# Fonte.net
KiCad netlist of a schematic drawn in Altium Designer
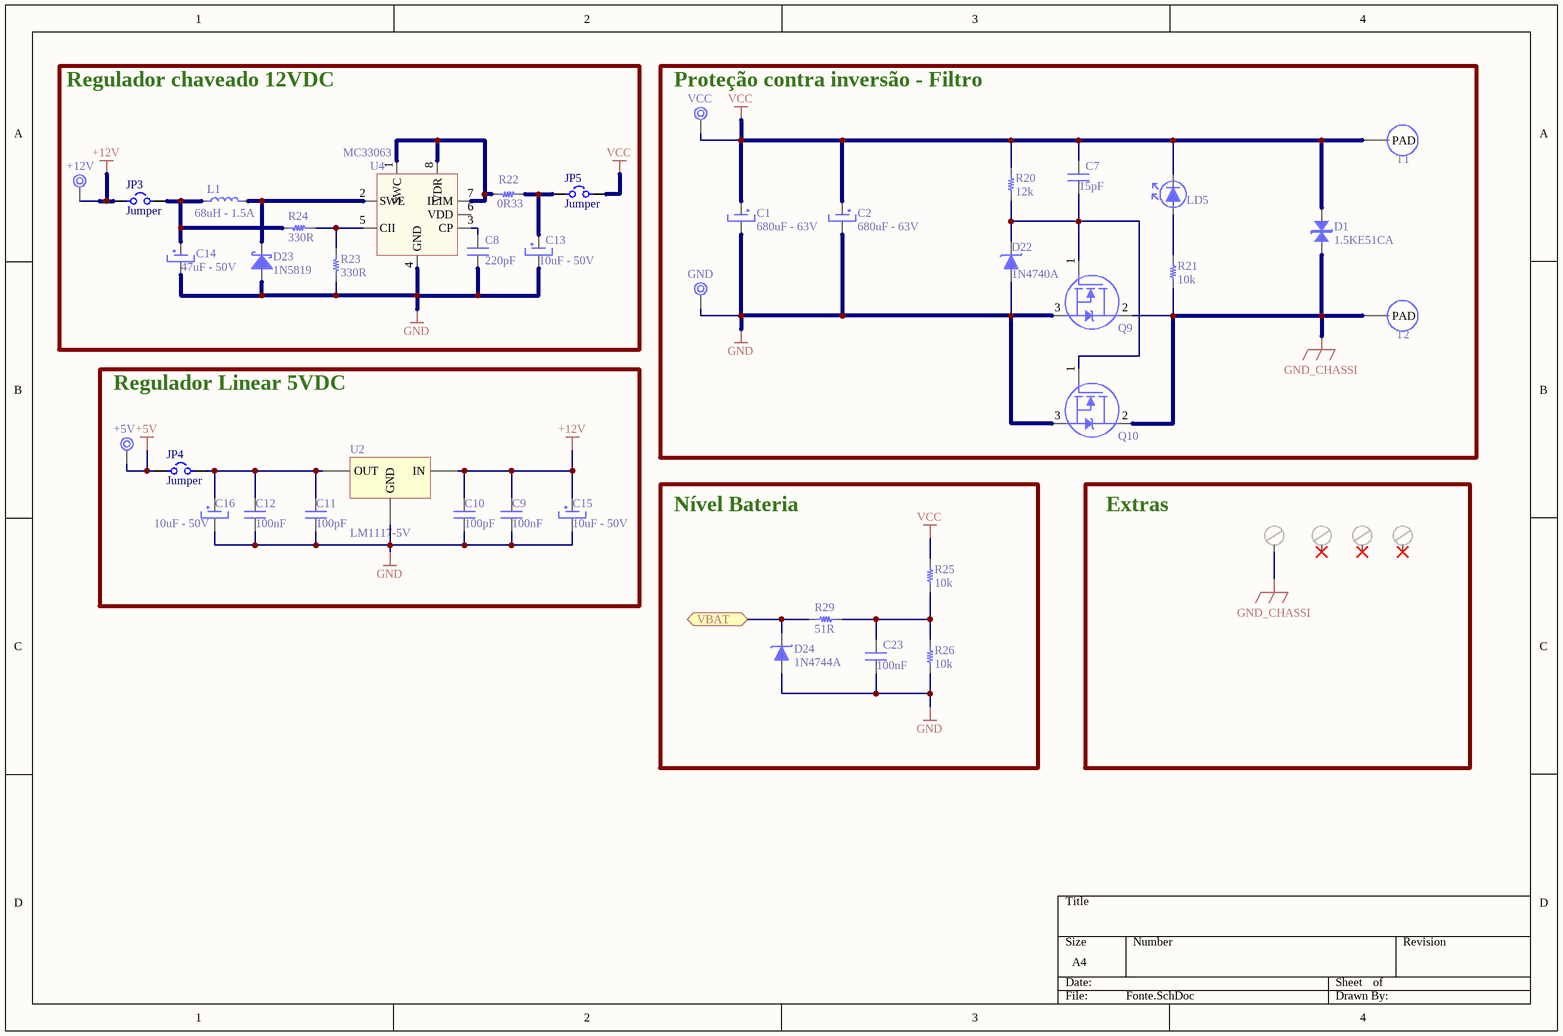
[diagram p0: Fonte.SchDoc]

(export (version "E")
  (design (tool "Eeschema 10.0.6"))
  (components
    (comp (ref "+5V") (value "+5V") (footprint "TEST_POINT") (libsource (lib "bike") (part "test_point")))
    (comp (ref "+12V") (value "+12V") (footprint "TEST_POINT") (libsource (lib "bike") (part "test_point")))
    (comp (ref "C1")
      (value "680uF - 63V")
      (footprint "Capacitor_PHT_filter")
      (description "Capacitor_680uF_63V")
      (libsource (lib "bike") (part "680uF - 63V"))
    )
    (comp (ref "C2")
      (value "680uF - 63V")
      (footprint "Capacitor_PHT_filter")
      (description "Capacitor_680uF_63V")
      (libsource (lib "bike") (part "680uF - 63V"))
    )
    (comp (ref "C7")
      (value "15pF")
      (footprint "Capacitor_0805")
      (description "Capacitor C0805 15pF")
      (libsource (lib "bike") (part "Cap0805_100nF"))
    )
    (comp (ref "C8")
      (value "220pF")
      (footprint "Capacitor_0805")
      (description "Capacitor C0805 100nF Desacoplamento")
      (libsource (lib "bike") (part "Cap0805_220pF"))
    )
    (comp (ref "C9")
      (value "100nF")
      (footprint "Capacitor_0805")
      (description "Capacitor C0805 100nF Desacoplamento")
      (libsource (lib "bike") (part "Cap0805_100nF"))
    )
    (comp (ref "C10")
      (value "100pF")
      (footprint "Capacitor_0805")
      (description "Capacitor C0805 100pF Desacoplamento")
      (libsource (lib "bike") (part "Cap0805_100nF"))
    )
    (comp (ref "C11")
      (value "100pF")
      (footprint "Capacitor_0805")
      (description "Capacitor C0805 100pF Desacoplamento")
      (libsource (lib "bike") (part "Cap0805_100nF"))
    )
    (comp (ref "C12")
      (value "100nF")
      (footprint "Capacitor_0805")
      (description "Capacitor C0805 100nF Desacoplamento")
      (libsource (lib "bike") (part "Cap0805_100nF"))
    )
    (comp (ref "C13")
      (value "10uF - 50V")
      (footprint "CAP_10x20mm")
      (description "Capacitor_10uF_50V")
      (libsource (lib "bike") (part "10uF - 50V"))
    )
    (comp (ref "C14")
      (value "47uF - 50V")
      (footprint "CAP_10x20mm")
      (description "Capacitor_47uF_50V")
      (libsource (lib "bike") (part "47uF - 50V"))
    )
    (comp (ref "C15")
      (value "10uF - 50V")
      (footprint "CAP_10x20mm")
      (description "Capacitor_10uF_50V")
      (libsource (lib "bike") (part "10uF - 50V"))
    )
    (comp (ref "C16")
      (value "10uF - 50V")
      (footprint "CAP_10x20mm")
      (description "Capacitor_10uF_50V")
      (libsource (lib "bike") (part "10uF - 50V"))
    )
    (comp (ref "C23")
      (value "100nF")
      (footprint "Capacitor_0805")
      (description "Capacitor C0805 100nF Desacoplamento")
      (libsource (lib "bike") (part "Cap0805_100nF"))
    )
    (comp (ref "D1")
      (value "1.5KE51CA")
      (footprint "DO-201")
      (description "Transzorb")
      (libsource (lib "bike") (part "1.5KE51CA"))
    )
    (comp (ref "D22")
      (value "1N4740A")
      (footprint "Diode_PHT")
      (description "Diodo Zener 10V 200mA")
      (libsource (lib "bike") (part "1N4740A"))
    )
    (comp (ref "D23")
      (value "1N5819")
      (footprint "Diode_PHT")
      (description "Diodo Schottky 40V - 1A")
      (libsource (lib "bike") (part "1N5819"))
    )
    (comp (ref "D24")
      (value "1N4744A")
      (footprint "Diode_PHT")
      (description "Diodo Zener 15V 200mA")
      (libsource (lib "bike") (part "1N4744A"))
    )
    (comp (ref "GND") (value "GND") (footprint "TEST_POINT") (libsource (lib "bike") (part "test_point")))
    (comp (ref "JP3")
      (value "Jumper")
      (footprint "JUMPER")
      (description "Jumper de solda")
      (libsource (lib "bike") (part "Jumper"))
    )
    (comp (ref "JP4")
      (value "Jumper")
      (footprint "JUMPER")
      (description "Jumper de solda")
      (libsource (lib "bike") (part "Jumper"))
    )
    (comp (ref "JP5")
      (value "Jumper")
      (footprint "JUMPER")
      (description "Jumper de solda")
      (libsource (lib "bike") (part "Jumper"))
    )
    (comp (ref "L1")
      (value "68uH - 1.5A")
      (footprint "Indutor_5mm")
      (description "Indutor Genérico PTH 5mm")
      (libsource (lib "bike") (part "Indutor_Genérico"))
    )
    (comp (ref "LD5")
      (value "Led")
      (footprint "Led 5mm")
      (description "Led padrão PTH ou SMD")
      (libsource (lib "bike") (part "Led"))
    )
    (comp (ref "PF1") (value "Screw M3") (footprint "Screw M3") (libsource (lib "bike") (part "Screw M3")))
    (comp (ref "PF2") (value "Screw M3") (footprint "Screw M3") (libsource (lib "bike") (part "Screw M3")))
    (comp (ref "PF3") (value "Screw M3") (footprint "Screw M3") (libsource (lib "bike") (part "Screw M3")))
    (comp (ref "PF4") (value "Screw M3") (footprint "Screw M3") (libsource (lib "bike") (part "Screw M3")))
    (comp (ref "Q9")
      (value "IRF1405")
      (footprint "TO-220AB")
      (description "MOSFET transistor")
      (libsource (lib "bike") (part "IRF1405"))
    )
    (comp (ref "Q10")
      (value "IRF1405")
      (footprint "TO-220AB")
      (description "MOSFET transistor")
      (libsource (lib "bike") (part "IRF1405"))
    )
    (comp (ref "R20")
      (value "12k")
      (footprint "R_0805")
      (description "Resistor padrão 0805")
      (libsource (lib "bike") (part "Resistor_12K"))
    )
    (comp (ref "R21")
      (value "10k")
      (footprint "R_0805")
      (description "Resistor padrão 0805")
      (libsource (lib "bike") (part "Resistor_10K"))
    )
    (comp (ref "R22")
      (value "0R33")
      (footprint "Resistor_PTH")
      (description "Resistor PHT")
      (libsource (lib "bike") (part "Resistor_Shunt_0R33"))
    )
    (comp (ref "R23")
      (value "330R")
      (footprint "R_0805")
      (description "Resistor padrão 0805")
      (libsource (lib "bike") (part "Resistor_330R"))
    )
    (comp (ref "R24")
      (value "330R")
      (footprint "R_0805")
      (description "Resistor padrão 0805")
      (libsource (lib "bike") (part "Resistor_330R"))
    )
    (comp (ref "R25")
      (value "10k")
      (footprint "R_0805")
      (description "Resistor padrão 0805")
      (libsource (lib "bike") (part "Resistor_10K"))
    )
    (comp (ref "R26")
      (value "10k")
      (footprint "R_0805")
      (description "Resistor padrão 0805")
      (libsource (lib "bike") (part "Resistor_10K"))
    )
    (comp (ref "R29")
      (value "51R")
      (footprint "R_0805")
      (description "Resistor padrão 0805")
      (libsource (lib "bike") (part "Resistor_10K"))
    )
    (comp (ref "T1")
      (value "Power_Pad")
      (footprint "Power_Pad")
      (description "Terminal de alta potência para soldar os cabos de potência")
      (libsource (lib "bike") (part "Power_Pad"))
    )
    (comp (ref "T2")
      (value "Power_Pad")
      (footprint "Power_Pad")
      (description "Terminal de alta potência para soldar os cabos de potência")
      (libsource (lib "bike") (part "Power_Pad"))
    )
    (comp (ref "U2")
      (value "LM1117-5V")
      (footprint "TO-252")
      (description "LM1117/LM1117I 800mA Low-Dropout Linear Regulator")
      (libsource (lib "bike") (part "LM1117-3V3"))
    )
    (comp (ref "U4")
      (value "MC33063")
      (footprint "DIP-8")
      (description "1.5-A Peak Boost/Buck/Inverting Switching Regulators")
      (libsource (lib "bike") (part "MC33063"))
    )
    (comp (ref "VCC") (value "VCC") (footprint "TEST_POINT") (libsource (lib "bike") (part "test_point")))
  )
  (nets
    (net (code "1") (name "+5V") (class "Default")
      (node (ref "+5V") (pin "1") (pinfunction "1_1") (pintype "passive"))
      (node (ref "JP4") (pin "1") (pinfunction "1_1") (pintype "passive"))
    )
    (net (code "2") (name "+12V") (class "Default")
      (node (ref "+12V") (pin "1") (pinfunction "1_1") (pintype "passive"))
      (node (ref "C10") (pin "2") (pinfunction "2_2") (pintype "passive"))
      (node (ref "C15") (pin "1") (pinfunction "1_1") (pintype "passive"))
      (node (ref "C9") (pin "2") (pinfunction "2_2") (pintype "passive"))
      (node (ref "JP3") (pin "1") (pinfunction "1_1") (pintype "passive"))
      (node (ref "U2") (pin "3") (pinfunction "IN_3") (pintype "power_in"))
    )
    (net (code "3") (name "/VBAT") (class "Default")
      (node (ref "D24") (pin "K") (pinfunction "Catodo_K") (pintype "passive"))
      (node (ref "R29") (pin "2") (pinfunction "2_2") (pintype "passive"))
    )
    (net (code "4") (name "GND") (class "Default")
      (node (ref "C1") (pin "1") (pinfunction "1_1") (pintype "passive"))
      (node (ref "C10") (pin "1") (pinfunction "1_1") (pintype "passive"))
      (node (ref "C11") (pin "1") (pinfunction "1_1") (pintype "passive"))
      (node (ref "C12") (pin "1") (pinfunction "1_1") (pintype "passive"))
      (node (ref "C13") (pin "2") (pinfunction "2_2") (pintype "passive"))
      (node (ref "C14") (pin "2") (pinfunction "2_2") (pintype "passive"))
      (node (ref "C15") (pin "2") (pinfunction "2_2") (pintype "passive"))
      (node (ref "C16") (pin "2") (pinfunction "2_2") (pintype "passive"))
      (node (ref "C2") (pin "1") (pinfunction "1_1") (pintype "passive"))
      (node (ref "C23") (pin "1") (pinfunction "1_1") (pintype "passive"))
      (node (ref "C8") (pin "1") (pinfunction "1_1") (pintype "passive"))
      (node (ref "C9") (pin "1") (pinfunction "1_1") (pintype "passive"))
      (node (ref "D22") (pin "A") (pinfunction "Anodo_A") (pintype "passive"))
      (node (ref "D23") (pin "A") (pinfunction "Anodo_A") (pintype "passive"))
      (node (ref "D24") (pin "A") (pinfunction "Anodo_A") (pintype "passive"))
      (node (ref "GND") (pin "1") (pinfunction "1_1") (pintype "passive"))
      (node (ref "Q10") (pin "3") (pinfunction "Source_3") (pintype "power_in"))
      (node (ref "Q9") (pin "3") (pinfunction "Source_3") (pintype "power_in"))
      (node (ref "R23") (pin "1") (pinfunction "1_1") (pintype "passive"))
      (node (ref "R26") (pin "1") (pinfunction "1_1") (pintype "passive"))
      (node (ref "U2") (pin "1") (pinfunction "GND_1") (pintype "power_in"))
      (node (ref "U4") (pin "4") (pinfunction "GND_4") (pintype "passive"))
    )
    (net (code "5") (name "GND_CHASSI") (class "Default")
      (node (ref "D1") (pin "A") (pinfunction "Anodo_A") (pintype "passive"))
      (node (ref "PF2") (pin "1") (pinfunction "1_1") (pintype "power_in"))
      (node (ref "Q10") (pin "2") (pinfunction "Drain_2") (pintype "power_in"))
      (node (ref "Q9") (pin "2") (pinfunction "Drain_2") (pintype "power_in"))
      (node (ref "R21") (pin "1") (pinfunction "1_1") (pintype "passive"))
      (node (ref "T2") (pin "1") (pinfunction "PAD_1") (pintype "power_in"))
    )
    (net (code "6") (name "Net-(C13-Pad1)") (class "Default")
      (node (ref "C13") (pin "1") (pinfunction "1_1") (pintype "passive"))
      (node (ref "JP5") (pin "1") (pinfunction "1_1") (pintype "passive"))
      (node (ref "R22") (pin "1") (pinfunction "1_1") (pintype "passive"))
    )
    (net (code "7") (name "Net-(C14-Pad1)") (class "Default")
      (node (ref "C14") (pin "1") (pinfunction "1_1") (pintype "passive"))
      (node (ref "JP3") (pin "2") (pinfunction "2_2") (pintype "passive"))
      (node (ref "L1") (pin "1") (pinfunction "1_1") (pintype "passive"))
      (node (ref "R24") (pin "1") (pinfunction "1_1") (pintype "passive"))
    )
    (net (code "8") (name "Net-(C23-Pad2)") (class "Default")
      (node (ref "C23") (pin "2") (pinfunction "2_2") (pintype "passive"))
      (node (ref "R25") (pin "1") (pinfunction "1_1") (pintype "passive"))
      (node (ref "R26") (pin "2") (pinfunction "2_2") (pintype "passive"))
      (node (ref "R29") (pin "1") (pinfunction "1_1") (pintype "passive"))
    )
    (net (code "9") (name "Net-(D22-Catodo)") (class "Default")
      (node (ref "C7") (pin "1") (pinfunction "1_1") (pintype "passive"))
      (node (ref "D22") (pin "K") (pinfunction "Catodo_K") (pintype "passive"))
      (node (ref "Q10") (pin "1") (pinfunction "Gate_1") (pintype "power_in"))
      (node (ref "Q9") (pin "1") (pinfunction "Gate_1") (pintype "power_in"))
      (node (ref "R20") (pin "1") (pinfunction "1_1") (pintype "passive"))
    )
    (net (code "10") (name "Net-(D23-Catodo)") (class "Default")
      (node (ref "D23") (pin "K") (pinfunction "Catodo_K") (pintype "passive"))
      (node (ref "L1") (pin "2") (pinfunction "2_2") (pintype "passive"))
      (node (ref "U4") (pin "2") (pinfunction "SWE_2") (pintype "passive"))
    )
    (net (code "11") (name "Net-(LD5-Anodo)") (class "Default")
      (node (ref "LD5") (pin "2") (pinfunction "Anodo_2") (pintype "passive"))
      (node (ref "R21") (pin "2") (pinfunction "2_2") (pintype "passive"))
    )
    (net (code "12") (name "Net-(U2-OUT)") (class "Default")
      (node (ref "C11") (pin "2") (pinfunction "2_2") (pintype "passive"))
      (node (ref "C12") (pin "2") (pinfunction "2_2") (pintype "passive"))
      (node (ref "C16") (pin "1") (pinfunction "1_1") (pintype "passive"))
      (node (ref "JP4") (pin "2") (pinfunction "2_2") (pintype "passive"))
      (node (ref "U2") (pin "4") (pinfunction "OUT_4") (pintype "power_in"))
    )
    (net (code "13") (name "Net-(U4-CII)") (class "Default")
      (node (ref "R23") (pin "2") (pinfunction "2_2") (pintype "passive"))
      (node (ref "R24") (pin "2") (pinfunction "2_2") (pintype "passive"))
      (node (ref "U4") (pin "5") (pinfunction "CII_5") (pintype "passive"))
    )
    (net (code "14") (name "Net-(U4-CP)") (class "Default")
      (node (ref "C8") (pin "2") (pinfunction "2_2") (pintype "passive"))
      (node (ref "U4") (pin "3") (pinfunction "CP_3") (pintype "passive"))
    )
    (net (code "15") (name "Net-(U4-ILIM)") (class "Default")
      (node (ref "R22") (pin "2") (pinfunction "2_2") (pintype "passive"))
      (node (ref "U4") (pin "1") (pinfunction "SWC_1") (pintype "passive"))
      (node (ref "U4") (pin "7") (pinfunction "ILIM_7") (pintype "passive"))
      (node (ref "U4") (pin "8") (pinfunction "VDR_8") (pintype "passive"))
    )
    (net (code "16") (name "VCC") (class "Default")
      (node (ref "C1") (pin "2") (pinfunction "2_2") (pintype "passive"))
      (node (ref "C2") (pin "2") (pinfunction "2_2") (pintype "passive"))
      (node (ref "C7") (pin "2") (pinfunction "2_2") (pintype "passive"))
      (node (ref "D1") (pin "K") (pinfunction "Catodo_K") (pintype "passive"))
      (node (ref "JP5") (pin "2") (pinfunction "2_2") (pintype "passive"))
      (node (ref "LD5") (pin "1") (pinfunction "Catodo_1") (pintype "passive"))
      (node (ref "R20") (pin "2") (pinfunction "2_2") (pintype "passive"))
      (node (ref "R25") (pin "2") (pinfunction "2_2") (pintype "passive"))
      (node (ref "T1") (pin "1") (pinfunction "PAD_1") (pintype "power_in"))
      (node (ref "VCC") (pin "1") (pinfunction "1_1") (pintype "passive"))
    )
    (net (code "17") (name "unconnected-(PF1-Pad1)") (class "Default")
      (node (ref "PF1") (pin "1") (pinfunction "1_1") (pintype "power_in+no_connect"))
    )
    (net (code "18") (name "unconnected-(PF3-Pad1)") (class "Default")
      (node (ref "PF3") (pin "1") (pinfunction "1_1") (pintype "power_in+no_connect"))
    )
    (net (code "19") (name "unconnected-(PF4-Pad1)") (class "Default")
      (node (ref "PF4") (pin "1") (pinfunction "1_1") (pintype "power_in+no_connect"))
    )
    (net (code "20") (name "unconnected-(U4-VDD-Pad6)") (class "Default")
      (node (ref "U4") (pin "6") (pinfunction "VDD_6") (pintype "passive"))
    )
  )
)
